# mlrs_lora_e5mini.net
KiCad netlist of a schematic drawn in EAGLE
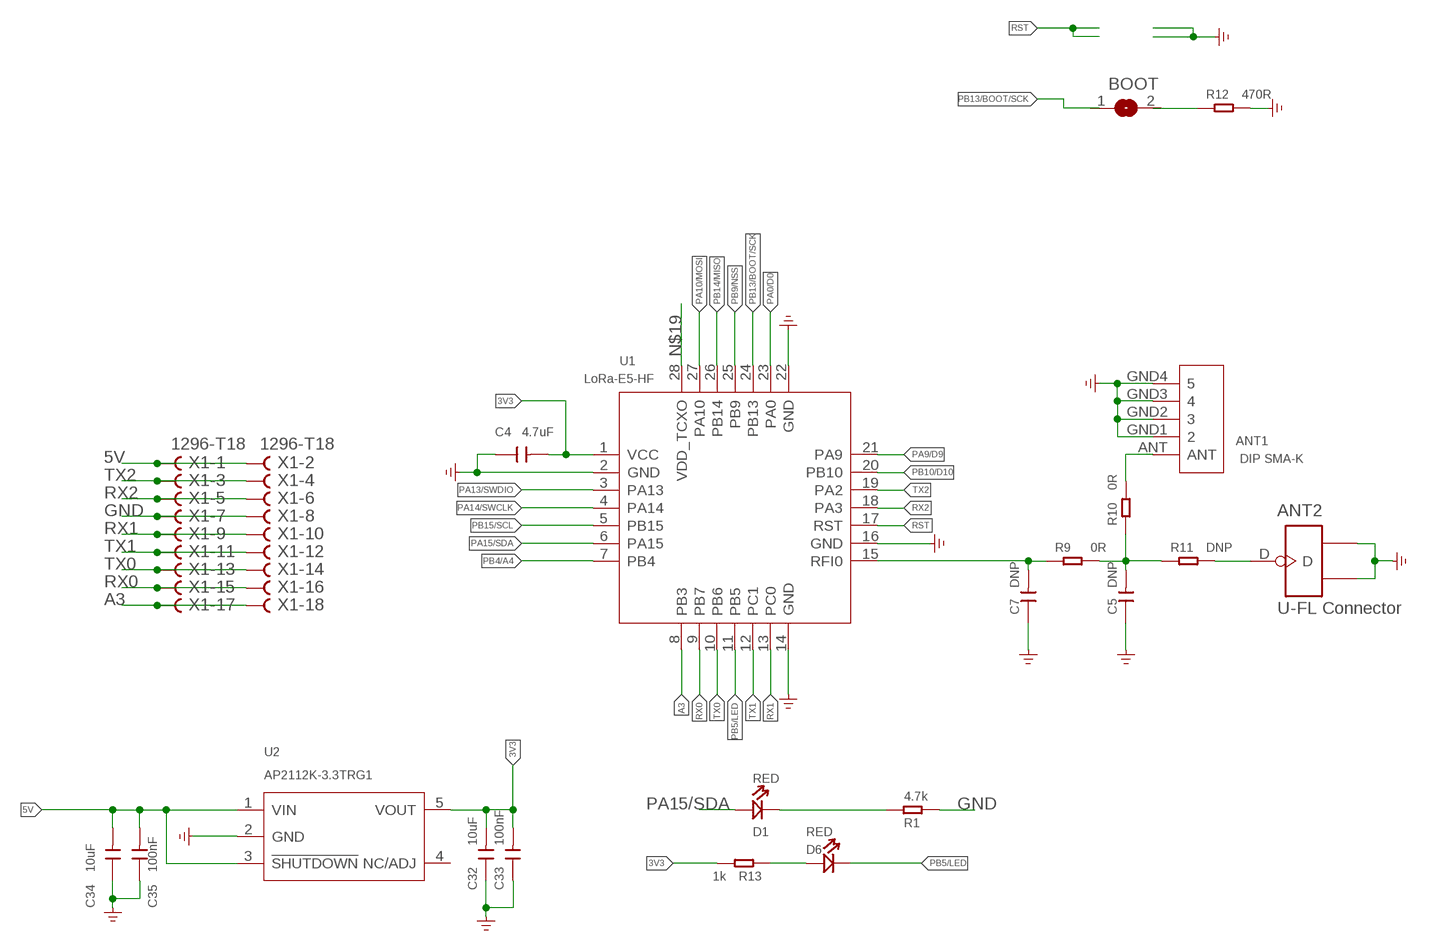
[diagram p0: schematic, sheet 1]

(export (version "E")
  (design (tool "Eeschema 10.0.6"))
  (components
    (comp (ref "ANT1")
      (value "DIP SMA-K")
      (footprint "eagle-import:SMA5P-SMD-5.1-6.5X6.5X16.5MM")
      (libsource (lib "eagle-import") (part "ANTENNA-SMA-MCX-JE-320160125"))
    )
    (comp (ref "ANT2")
      (value "U-FL Connector")
      (footprint "eagle-import:U-FL3P-SMD-2.6X2.6X1.0MM")
      (libsource (lib "eagle-import") (part "ANTENNA-U-FL-320110048"))
    )
    (comp (ref "BOOT")
      (value "SJ")
      (footprint "eagle-import:SJ")
      (libsource (lib "eagle-import") (part "SJ"))
    )
    (comp (ref "C4")
      (value "4.7uF")
      (footprint "eagle-import:C0603")
      (libsource (lib "eagle-import") (part "CAP-0603"))
    )
    (comp (ref "C5")
      (value "DNP")
      (footprint "eagle-import:C0402")
      (libsource (lib "eagle-import") (part "CAP-0402"))
    )
    (comp (ref "C7")
      (value "DNP")
      (footprint "eagle-import:C0402")
      (libsource (lib "eagle-import") (part "CAP-0402"))
    )
    (comp (ref "C32")
      (value "10uF")
      (footprint "eagle-import:C0805")
      (libsource (lib "eagle-import") (part "CAP-0805"))
    )
    (comp (ref "C33")
      (value "100nF")
      (footprint "eagle-import:C0603")
      (libsource (lib "eagle-import") (part "CAP-0603"))
    )
    (comp (ref "C34")
      (value "10uF")
      (footprint "eagle-import:C0805")
      (libsource (lib "eagle-import") (part "CAP-0805"))
    )
    (comp (ref "C35")
      (value "100nF")
      (footprint "eagle-import:C0603")
      (libsource (lib "eagle-import") (part "CAP-0603"))
    )
    (comp (ref "D1")
      (value "RED")
      (footprint "eagle-import:LED-0603")
      (libsource (lib "eagle-import") (part "LED'0603'"))
    )
    (comp (ref "D6")
      (value "RED")
      (footprint "eagle-import:LED-0603")
      (libsource (lib "eagle-import") (part "LED'0603'"))
    )
    (comp (ref "R1")
      (value "4.7k")
      (footprint "eagle-import:R0402")
      (libsource (lib "eagle-import") (part "RES-0402"))
    )
    (comp (ref "R9")
      (value "0R")
      (footprint "eagle-import:R0402")
      (libsource (lib "eagle-import") (part "RES-0402"))
    )
    (comp (ref "R10")
      (value "0R")
      (footprint "eagle-import:R0402")
      (libsource (lib "eagle-import") (part "RES-0402"))
    )
    (comp (ref "R11")
      (value "DNP")
      (footprint "eagle-import:R0402")
      (libsource (lib "eagle-import") (part "RES-0402"))
    )
    (comp (ref "R12")
      (value "470R")
      (footprint "eagle-import:R0402")
      (libsource (lib "eagle-import") (part "RES-0402"))
    )
    (comp (ref "R13")
      (value "1k")
      (footprint "eagle-import:R0402")
      (libsource (lib "eagle-import") (part "RES-0402"))
    )
    (comp (ref "U1")
      (value "LoRa-E5-HF")
      (footprint "eagle-import:MOUDLE28P-1.25-12X12X2.5MM")
      (libsource (lib "eagle-import") (part "MOUDLE_LORA_E5"))
    )
    (comp (ref "U2")
      (value "AP2112K-3.3TRG1")
      (footprint "eagle-import:SOT-23-5")
      (libsource (lib "eagle-import") (part "PMIC-AP2127"))
    )
    (comp (ref "X1")
      (value "1296-T18")
      (footprint "eagle-import:1296-18")
      (libsource (lib "eagle-import") (part "1296-T18"))
    )
  )
  (nets
    (net (code "1") (name "/N$19") (class "Default")
      (node (ref "U1") (pin "28") (pinfunction "VDD_TCXO_28") (pintype "bidirectional"))
    )
    (net (code "2") (name "3V3") (class "Default")
      (node (ref "C32") (pin "2") (pinfunction "2_2") (pintype "passive"))
      (node (ref "C33") (pin "2") (pinfunction "2_2") (pintype "passive"))
      (node (ref "C4") (pin "2") (pinfunction "2_2") (pintype "passive"))
      (node (ref "R13") (pin "2") (pinfunction "2_2") (pintype "passive"))
      (node (ref "U1") (pin "1") (pinfunction "VCC_1") (pintype "bidirectional"))
      (node (ref "U2") (pin "5") (pinfunction "VOUT_5") (pintype "bidirectional"))
    )
    (net (code "3") (name "5V") (class "Default")
      (node (ref "C34") (pin "2") (pinfunction "2_2") (pintype "passive"))
      (node (ref "C35") (pin "2") (pinfunction "2_2") (pintype "passive"))
      (node (ref "U2") (pin "1") (pinfunction "VIN_1") (pintype "bidirectional"))
      (node (ref "U2") (pin "3") (pinfunction "~{SHUTDOWN}_3") (pintype "bidirectional"))
      (node (ref "X1") (pin "1") (pinfunction "B_1") (pintype "passive"))
      (node (ref "X1") (pin "2") (pinfunction "B_2") (pintype "passive"))
    )
    (net (code "4") (name "A3") (class "Default")
      (node (ref "U1") (pin "8") (pinfunction "PB3_8") (pintype "bidirectional"))
      (node (ref "X1") (pin "17") (pinfunction "B_17") (pintype "passive"))
      (node (ref "X1") (pin "18") (pinfunction "B_18") (pintype "passive"))
    )
    (net (code "5") (name "GND_POWER") (class "Default")
      (node (ref "ANT1") (pin "GND1") (pinfunction "2_GND1") (pintype "bidirectional"))
      (node (ref "ANT1") (pin "GND2") (pinfunction "3_GND2") (pintype "bidirectional"))
      (node (ref "ANT1") (pin "GND3") (pinfunction "4_GND3") (pintype "bidirectional"))
      (node (ref "ANT1") (pin "GND4") (pinfunction "5_GND4") (pintype "bidirectional"))
      (node (ref "ANT2") (pin "GND1") (pinfunction "GND1_GND1") (pintype "bidirectional"))
      (node (ref "ANT2") (pin "GND2") (pinfunction "GND2_GND2") (pintype "bidirectional"))
      (node (ref "C32") (pin "1") (pinfunction "1_1") (pintype "passive"))
      (node (ref "C33") (pin "1") (pinfunction "1_1") (pintype "passive"))
      (node (ref "C34") (pin "1") (pinfunction "1_1") (pintype "passive"))
      (node (ref "C35") (pin "1") (pinfunction "1_1") (pintype "passive"))
      (node (ref "C4") (pin "1") (pinfunction "1_1") (pintype "passive"))
      (node (ref "C5") (pin "1") (pinfunction "1_1") (pintype "passive"))
      (node (ref "C7") (pin "1") (pinfunction "1_1") (pintype "passive"))
      (node (ref "R1") (pin "2") (pinfunction "2_2") (pintype "passive"))
      (node (ref "R12") (pin "2") (pinfunction "2_2") (pintype "passive"))
      (node (ref "U1") (pin "14") (pinfunction "GND_14") (pintype "bidirectional"))
      (node (ref "U1") (pin "16") (pinfunction "GND_16") (pintype "bidirectional"))
      (node (ref "U1") (pin "2") (pinfunction "GND_2") (pintype "bidirectional"))
      (node (ref "U1") (pin "22") (pinfunction "GND_22") (pintype "bidirectional"))
      (node (ref "U2") (pin "2") (pinfunction "GND_2") (pintype "bidirectional"))
      (node (ref "X1") (pin "7") (pinfunction "B_7") (pintype "passive"))
      (node (ref "X1") (pin "8") (pinfunction "B_8") (pintype "passive"))
    )
    (net (code "6") (name "Net-(ANT1-PadANT)") (class "Default")
      (node (ref "ANT1") (pin "ANT") (pinfunction "ANT_ANT") (pintype "bidirectional"))
      (node (ref "R10") (pin "2") (pinfunction "2_2") (pintype "passive"))
    )
    (net (code "7") (name "Net-(ANT2-PadD)") (class "Default")
      (node (ref "ANT2") (pin "D") (pinfunction "D_D") (pintype "bidirectional"))
      (node (ref "R11") (pin "2") (pinfunction "2_2") (pintype "passive"))
    )
    (net (code "8") (name "Net-(BOOT-Pad2)") (class "Default")
      (node (ref "BOOT") (pin "2") (pinfunction "2_2") (pintype "passive"))
      (node (ref "R12") (pin "1") (pinfunction "1_1") (pintype "passive"))
    )
    (net (code "9") (name "Net-(C5-Pad2)") (class "Default")
      (node (ref "C5") (pin "2") (pinfunction "2_2") (pintype "passive"))
      (node (ref "R10") (pin "1") (pinfunction "1_1") (pintype "passive"))
      (node (ref "R11") (pin "1") (pinfunction "1_1") (pintype "passive"))
      (node (ref "R9") (pin "2") (pinfunction "2_2") (pintype "passive"))
    )
    (net (code "10") (name "Net-(D1-Pad-)") (class "Default")
      (node (ref "D1") (pin "-") (pinfunction "-_-") (pintype "passive"))
      (node (ref "R1") (pin "1") (pinfunction "1_1") (pintype "passive"))
    )
    (net (code "11") (name "Net-(D6-Pad+)") (class "Default")
      (node (ref "D6") (pin "+") (pinfunction "+_+") (pintype "passive"))
      (node (ref "R13") (pin "1") (pinfunction "1_1") (pintype "passive"))
    )
    (net (code "12") (name "Net-(U1-RFI0)") (class "Default")
      (node (ref "C7") (pin "2") (pinfunction "2_2") (pintype "passive"))
      (node (ref "R9") (pin "1") (pinfunction "1_1") (pintype "passive"))
      (node (ref "U1") (pin "15") (pinfunction "RFI0_15") (pintype "bidirectional"))
    )
    (net (code "13") (name "PA0{slash}D0") (class "Default")
      (node (ref "U1") (pin "23") (pinfunction "PA0_23") (pintype "bidirectional"))
    )
    (net (code "14") (name "PA9{slash}D9") (class "Default")
      (node (ref "U1") (pin "21") (pinfunction "PA9_21") (pintype "bidirectional"))
    )
    (net (code "15") (name "PA10{slash}MOSI") (class "Default")
      (node (ref "U1") (pin "27") (pinfunction "PA10_27") (pintype "bidirectional"))
    )
    (net (code "16") (name "PA13{slash}SWDIO") (class "Default")
      (node (ref "U1") (pin "3") (pinfunction "PA13_3") (pintype "bidirectional"))
    )
    (net (code "17") (name "PA14{slash}SWCLK") (class "Default")
      (node (ref "U1") (pin "4") (pinfunction "PA14_4") (pintype "bidirectional"))
    )
    (net (code "18") (name "PA15{slash}SDA") (class "Default")
      (node (ref "D1") (pin "+") (pinfunction "+_+") (pintype "passive"))
      (node (ref "U1") (pin "6") (pinfunction "PA15_6") (pintype "bidirectional"))
    )
    (net (code "19") (name "PB4{slash}A4") (class "Default")
      (node (ref "U1") (pin "7") (pinfunction "PB4_7") (pintype "bidirectional"))
    )
    (net (code "20") (name "PB5{slash}LED") (class "Default")
      (node (ref "D6") (pin "-") (pinfunction "-_-") (pintype "passive"))
      (node (ref "U1") (pin "11") (pinfunction "PB5_11") (pintype "bidirectional"))
    )
    (net (code "21") (name "PB9{slash}NSS") (class "Default")
      (node (ref "U1") (pin "25") (pinfunction "PB9_25") (pintype "bidirectional"))
    )
    (net (code "22") (name "PB10{slash}D10") (class "Default")
      (node (ref "U1") (pin "20") (pinfunction "PB10_20") (pintype "bidirectional"))
    )
    (net (code "23") (name "PB13{slash}BOOT{slash}SCK") (class "Default")
      (node (ref "BOOT") (pin "1") (pinfunction "1_1") (pintype "passive"))
      (node (ref "U1") (pin "24") (pinfunction "PB13_24") (pintype "bidirectional"))
    )
    (net (code "24") (name "PB14{slash}MISO") (class "Default")
      (node (ref "U1") (pin "26") (pinfunction "PB14_26") (pintype "bidirectional"))
    )
    (net (code "25") (name "PB15{slash}SCL") (class "Default")
      (node (ref "U1") (pin "5") (pinfunction "PB15_5") (pintype "bidirectional"))
    )
    (net (code "26") (name "RST") (class "Default")
      (node (ref "U1") (pin "17") (pinfunction "RST_17") (pintype "bidirectional"))
    )
    (net (code "27") (name "RX0") (class "Default")
      (node (ref "U1") (pin "9") (pinfunction "PB7_9") (pintype "bidirectional"))
      (node (ref "X1") (pin "15") (pinfunction "B_15") (pintype "passive"))
      (node (ref "X1") (pin "16") (pinfunction "B_16") (pintype "passive"))
    )
    (net (code "28") (name "RX1") (class "Default")
      (node (ref "U1") (pin "13") (pinfunction "PC0_13") (pintype "bidirectional"))
      (node (ref "X1") (pin "10") (pinfunction "B_10") (pintype "passive"))
      (node (ref "X1") (pin "9") (pinfunction "B_9") (pintype "passive"))
    )
    (net (code "29") (name "RX2") (class "Default")
      (node (ref "U1") (pin "18") (pinfunction "PA3_18") (pintype "bidirectional"))
      (node (ref "X1") (pin "5") (pinfunction "B_5") (pintype "passive"))
      (node (ref "X1") (pin "6") (pinfunction "B_6") (pintype "passive"))
    )
    (net (code "30") (name "TX0") (class "Default")
      (node (ref "U1") (pin "10") (pinfunction "PB6_10") (pintype "bidirectional"))
      (node (ref "X1") (pin "13") (pinfunction "B_13") (pintype "passive"))
      (node (ref "X1") (pin "14") (pinfunction "B_14") (pintype "passive"))
    )
    (net (code "31") (name "TX1") (class "Default")
      (node (ref "U1") (pin "12") (pinfunction "PC1_12") (pintype "bidirectional"))
      (node (ref "X1") (pin "11") (pinfunction "B_11") (pintype "passive"))
      (node (ref "X1") (pin "12") (pinfunction "B_12") (pintype "passive"))
    )
    (net (code "32") (name "TX2") (class "Default")
      (node (ref "U1") (pin "19") (pinfunction "PA2_19") (pintype "bidirectional"))
      (node (ref "X1") (pin "3") (pinfunction "B_3") (pintype "passive"))
      (node (ref "X1") (pin "4") (pinfunction "B_4") (pintype "passive"))
    )
    (net (code "33") (name "unconnected-(U2-NC{slash}ADJ-Pad4)") (class "Default")
      (node (ref "U2") (pin "4") (pinfunction "NC/ADJ_4") (pintype "bidirectional"))
    )
  )
)
